# audioRev5.net
KiCad netlist of a schematic drawn in EAGLE
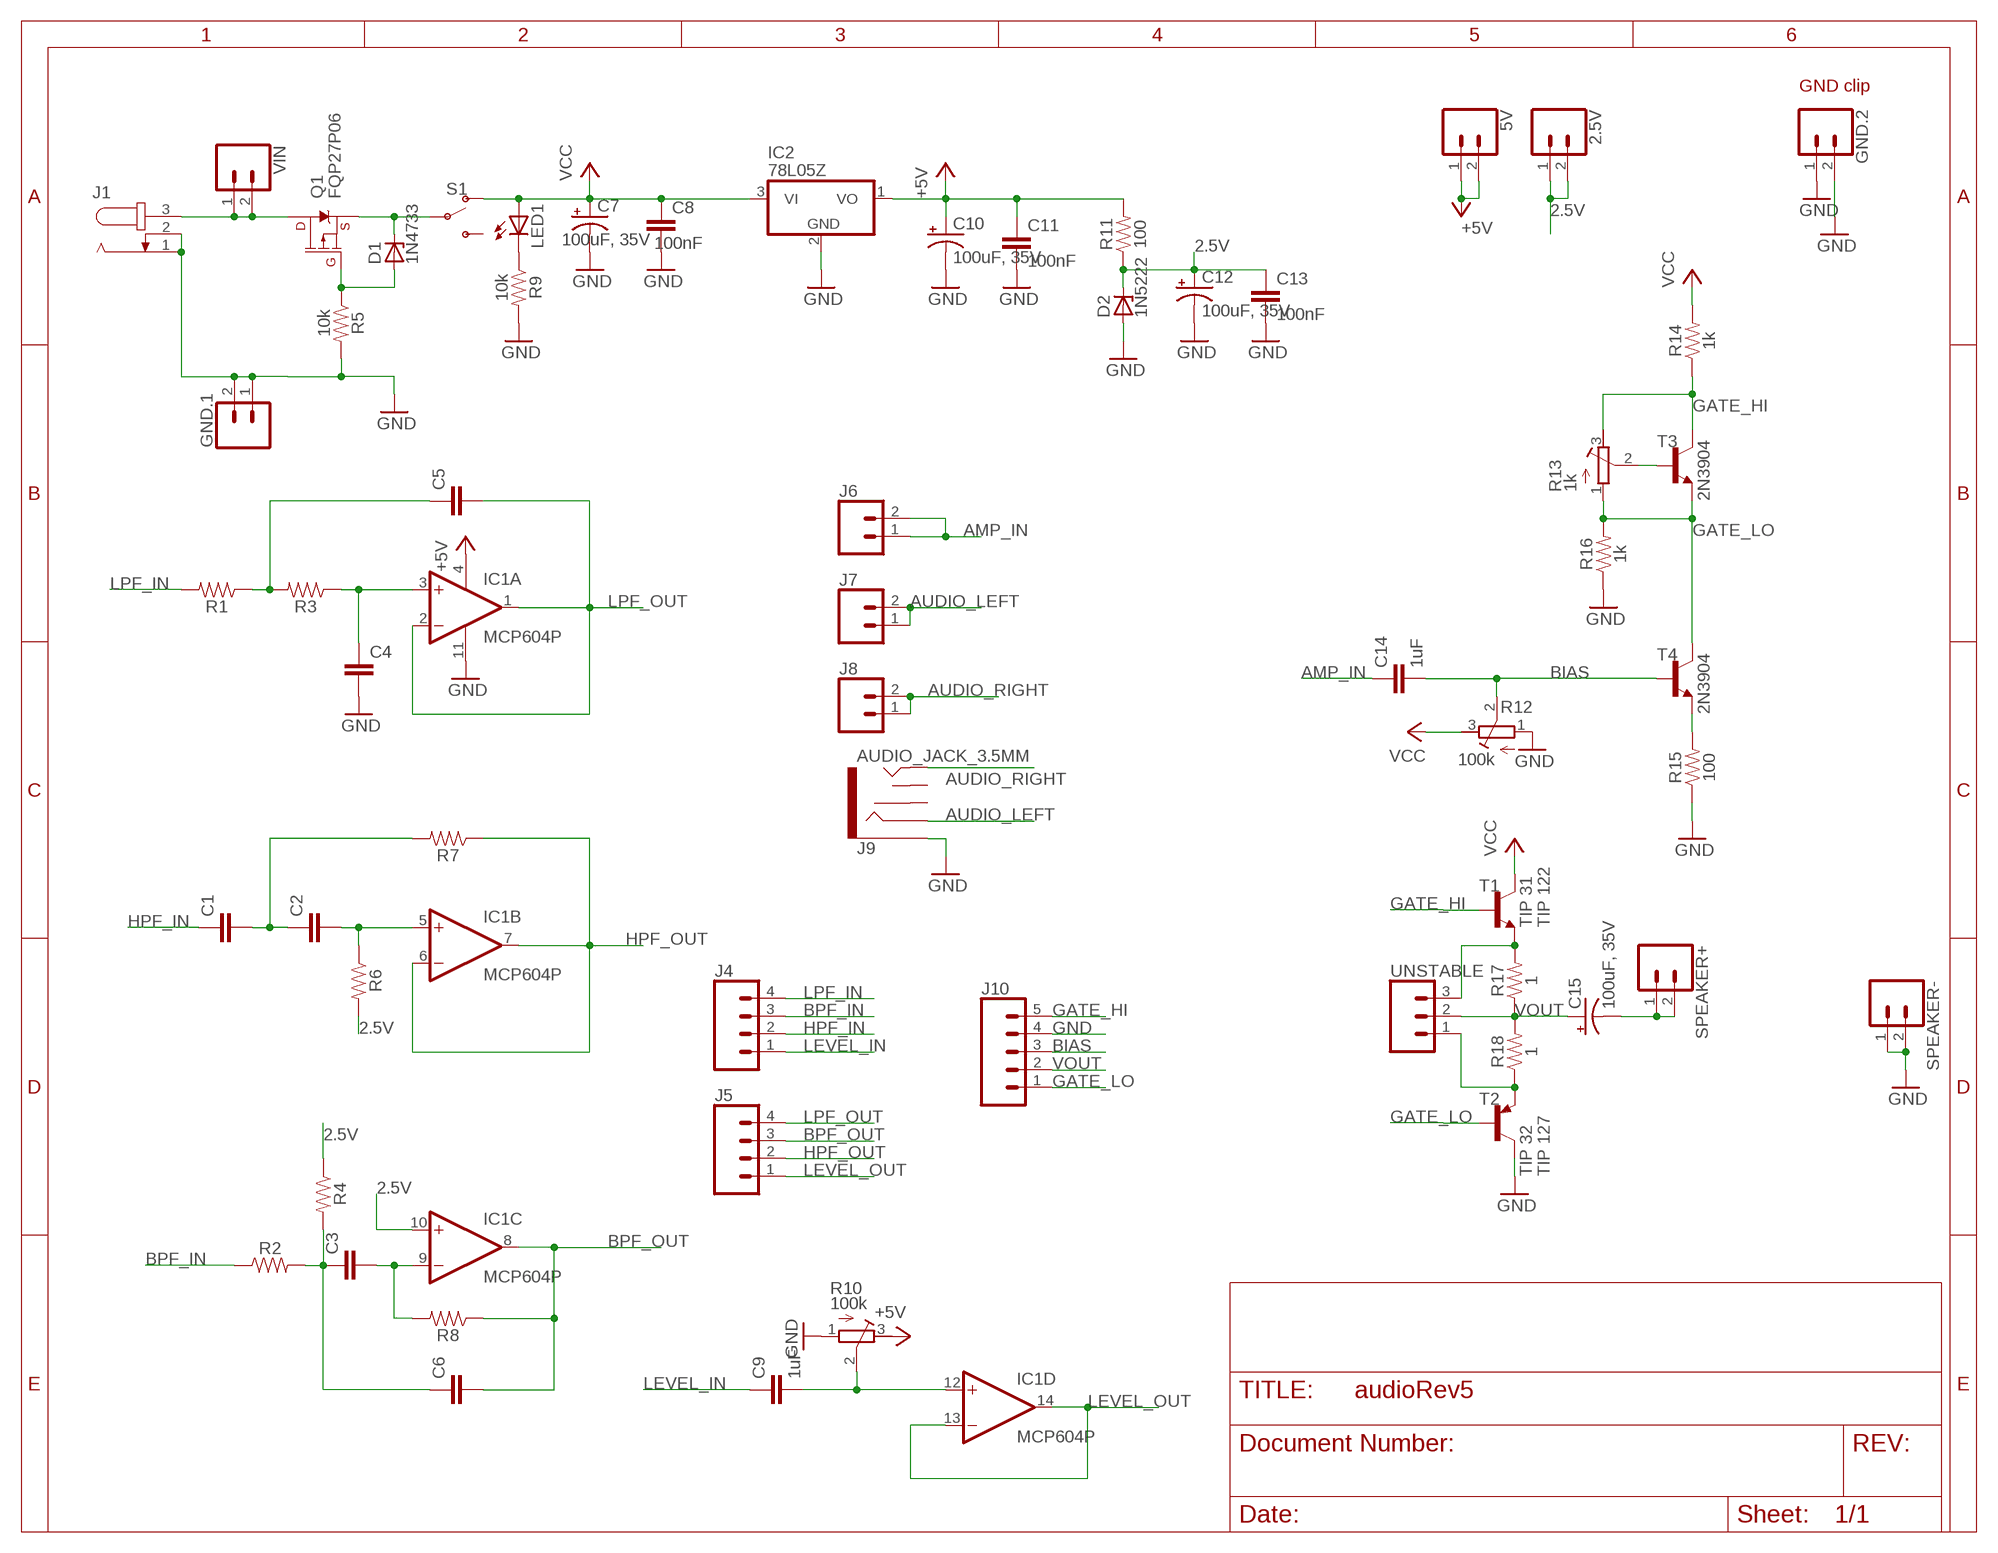
[diagram p0: schematic, sheet 1]

(export (version "E")
  (design (tool "Eeschema 10.0.6"))
  (components
    (comp (ref "2.5V")
      (value "CONN_02")
      (footprint "eagle-import:1X02")
      (libsource (lib "eagle-import") (part "CONN_02"))
    )
    (comp (ref "5V")
      (value "CONN_02")
      (footprint "eagle-import:1X02")
      (libsource (lib "eagle-import") (part "CONN_02"))
    )
    (comp (ref "C1")
      (value "C-EU025-025X050")
      (footprint "eagle-import:C025-025X050")
      (libsource (lib "eagle-import") (part "C-EU025-025X050"))
    )
    (comp (ref "C2")
      (value "C-EU025-025X050")
      (footprint "eagle-import:C025-025X050")
      (libsource (lib "eagle-import") (part "C-EU025-025X050"))
    )
    (comp (ref "C3")
      (value "C-EU025-025X050")
      (footprint "eagle-import:C025-025X050")
      (libsource (lib "eagle-import") (part "C-EU025-025X050"))
    )
    (comp (ref "C4")
      (value "C-EU025-025X050")
      (footprint "eagle-import:C025-025X050")
      (libsource (lib "eagle-import") (part "C-EU025-025X050"))
    )
    (comp (ref "C5")
      (value "C-EU025-025X050")
      (footprint "eagle-import:C025-025X050")
      (libsource (lib "eagle-import") (part "C-EU025-025X050"))
    )
    (comp (ref "C6")
      (value "C-EU025-025X050")
      (footprint "eagle-import:C025-025X050")
      (libsource (lib "eagle-import") (part "C-EU025-025X050"))
    )
    (comp (ref "C7")
      (value "100uF, 35V")
      (footprint "eagle-import:E2,5-6")
      (libsource (lib "eagle-import") (part "CPOL-USE2.5-6"))
    )
    (comp (ref "C8")
      (value "100nF")
      (footprint "eagle-import:C025-025X050")
      (libsource (lib "eagle-import") (part "C-EU025-025X050"))
    )
    (comp (ref "C9")
      (value "1uF")
      (footprint "eagle-import:C025-025X050")
      (libsource (lib "eagle-import") (part "C-EU025-025X050"))
    )
    (comp (ref "C10")
      (value "100uF, 35V")
      (footprint "eagle-import:E2,5-6")
      (libsource (lib "eagle-import") (part "CPOL-USE2.5-6"))
    )
    (comp (ref "C11")
      (value "100nF")
      (footprint "eagle-import:C025-025X050")
      (libsource (lib "eagle-import") (part "C-EU025-025X050"))
    )
    (comp (ref "C12")
      (value "100uF, 35V")
      (footprint "eagle-import:E2,5-6")
      (libsource (lib "eagle-import") (part "CPOL-USE2.5-6"))
    )
    (comp (ref "C13")
      (value "100nF")
      (footprint "eagle-import:C025-025X050")
      (libsource (lib "eagle-import") (part "C-EU025-025X050"))
    )
    (comp (ref "C14")
      (value "1uF")
      (footprint "eagle-import:C025-025X050")
      (libsource (lib "eagle-import") (part "C-EU025-025X050"))
    )
    (comp (ref "C15")
      (value "100uF, 35V")
      (footprint "eagle-import:E2,5-6")
      (libsource (lib "eagle-import") (part "CPOL-USE2.5-6"))
    )
    (comp (ref "D1")
      (value "1N4733")
      (footprint "eagle-import:DO41Z10")
      (libsource (lib "eagle-import") (part "ZENER-DIODEDO41Z10"))
    )
    (comp (ref "D2")
      (value "1N5222")
      (footprint "eagle-import:DO34Z7")
      (libsource (lib "eagle-import") (part "ZENER-DIODEDO34-7"))
    )
    (comp (ref "GND.1")
      (value "CONN_02")
      (footprint "eagle-import:1X02")
      (libsource (lib "eagle-import") (part "CONN_02"))
    )
    (comp (ref "GND.2")
      (value "CONN_02")
      (footprint "eagle-import:1X02")
      (libsource (lib "eagle-import") (part "CONN_02"))
    )
    (comp (ref "IC1")
      (value "MCP604P")
      (footprint "eagle-import:DIL14")
      (libsource (lib "eagle-import") (part "MCP604P"))
    )
    (comp (ref "IC2")
      (value "78L05Z")
      (footprint "eagle-import:TO92")
      (libsource (lib "eagle-import") (part "78ZL05"))
    )
    (comp (ref "J1")
      (value "JACK-PLUG0")
      (footprint "eagle-import:SPC4077")
      (libsource (lib "eagle-import") (part "JACK-PLUG0"))
    )
    (comp (ref "J4")
      (value "CONN_04LOCK_LONGPADS")
      (footprint "eagle-import:1X04_LOCK_LONGPADS")
      (libsource (lib "eagle-import") (part "CONN_04LOCK_LONGPADS"))
    )
    (comp (ref "J5")
      (value "CONN_04LOCK_LONGPADS")
      (footprint "eagle-import:1X04_LOCK_LONGPADS")
      (libsource (lib "eagle-import") (part "CONN_04LOCK_LONGPADS"))
    )
    (comp (ref "J6")
      (value "CONN_02")
      (footprint "eagle-import:1X02")
      (libsource (lib "eagle-import") (part "CONN_02"))
    )
    (comp (ref "J7")
      (value "CONN_02")
      (footprint "eagle-import:1X02")
      (libsource (lib "eagle-import") (part "CONN_02"))
    )
    (comp (ref "J8")
      (value "CONN_02")
      (footprint "eagle-import:1X02")
      (libsource (lib "eagle-import") (part "CONN_02"))
    )
    (comp (ref "J9")
      (value "AUDIO_JACK_3.5MM")
      (footprint "eagle-import:AUDIO-JACK")
      (libsource (lib "eagle-import") (part "AUDIO_JACK_3.5MM_PTH"))
    )
    (comp (ref "J10")
      (value "CONN_05PTH_LONGPADS")
      (footprint "eagle-import:1X05_LONGPADS")
      (libsource (lib "eagle-import") (part "CONN_05PTH_LONGPADS"))
    )
    (comp (ref "LED1")
      (value "LED5MM")
      (footprint "eagle-import:LED5MM")
      (libsource (lib "eagle-import") (part "LED5MM"))
    )
    (comp (ref "Q1")
      (value "FQP27P06")
      (footprint "eagle-import:TO220V")
      (libsource (lib "eagle-import") (part "MOSFET_PCH-NDP6020P"))
    )
    (comp (ref "R1")
      (value "RESISTORAXIAL-0.3")
      (footprint "eagle-import:AXIAL-0.3")
      (libsource (lib "eagle-import") (part "RESISTORAXIAL-0.3"))
    )
    (comp (ref "R2")
      (value "RESISTORAXIAL-0.3")
      (footprint "eagle-import:AXIAL-0.3")
      (libsource (lib "eagle-import") (part "RESISTORAXIAL-0.3"))
    )
    (comp (ref "R3")
      (value "RESISTORAXIAL-0.3")
      (footprint "eagle-import:AXIAL-0.3")
      (libsource (lib "eagle-import") (part "RESISTORAXIAL-0.3"))
    )
    (comp (ref "R4")
      (value "RESISTORAXIAL-0.3")
      (footprint "eagle-import:AXIAL-0.3")
      (libsource (lib "eagle-import") (part "RESISTORAXIAL-0.3"))
    )
    (comp (ref "R5")
      (value "10k")
      (footprint "eagle-import:AXIAL-0.3")
      (libsource (lib "eagle-import") (part "RESISTORAXIAL-0.3"))
    )
    (comp (ref "R6")
      (value "RESISTORAXIAL-0.3")
      (footprint "eagle-import:AXIAL-0.3")
      (libsource (lib "eagle-import") (part "RESISTORAXIAL-0.3"))
    )
    (comp (ref "R7")
      (value "RESISTORAXIAL-0.3")
      (footprint "eagle-import:AXIAL-0.3")
      (libsource (lib "eagle-import") (part "RESISTORAXIAL-0.3"))
    )
    (comp (ref "R8")
      (value "RESISTORAXIAL-0.3")
      (footprint "eagle-import:AXIAL-0.3")
      (libsource (lib "eagle-import") (part "RESISTORAXIAL-0.3"))
    )
    (comp (ref "R9")
      (value "10k")
      (footprint "eagle-import:AXIAL-0.3")
      (libsource (lib "eagle-import") (part "RESISTORAXIAL-0.3"))
    )
    (comp (ref "R10")
      (value "100k")
      (footprint "eagle-import:RTRIM3296W")
      (libsource (lib "eagle-import") (part "R-TRIMM3296W"))
    )
    (comp (ref "R11")
      (value "100")
      (footprint "eagle-import:AXIAL-0.3")
      (libsource (lib "eagle-import") (part "RESISTORAXIAL-0.3"))
    )
    (comp (ref "R12")
      (value "100k")
      (footprint "eagle-import:RTRIM3296W")
      (libsource (lib "eagle-import") (part "R-TRIMM3296W"))
    )
    (comp (ref "R13")
      (value "1k")
      (footprint "eagle-import:RTRIM3296W")
      (libsource (lib "eagle-import") (part "R-TRIMM3296W"))
    )
    (comp (ref "R14")
      (value "1k")
      (footprint "eagle-import:AXIAL-0.3")
      (libsource (lib "eagle-import") (part "RESISTORAXIAL-0.3"))
    )
    (comp (ref "R15")
      (value "100")
      (footprint "eagle-import:AXIAL-0.3")
      (libsource (lib "eagle-import") (part "RESISTORAXIAL-0.3"))
    )
    (comp (ref "R16")
      (value "1k")
      (footprint "eagle-import:AXIAL-0.3")
      (libsource (lib "eagle-import") (part "RESISTORAXIAL-0.3"))
    )
    (comp (ref "R17")
      (value "1")
      (footprint "eagle-import:AXIAL-0.3")
      (libsource (lib "eagle-import") (part "RESISTORAXIAL-0.3"))
    )
    (comp (ref "R18")
      (value "1")
      (footprint "eagle-import:AXIAL-0.3")
      (libsource (lib "eagle-import") (part "RESISTORAXIAL-0.3"))
    )
    (comp (ref "S1")
      (value "SWITCH-SPDT-PTH-11.6X4.0MM")
      (footprint "eagle-import:SWITCH_SPDT_PTH_11.6X4.0MM")
      (libsource (lib "eagle-import") (part "SWITCH-SPDT-PTH-11.6X4.0MM"))
    )
    (comp (ref "SPEAKER+")
      (value "CONN_02")
      (footprint "eagle-import:1X02")
      (libsource (lib "eagle-import") (part "CONN_02"))
    )
    (comp (ref "SPEAKER-")
      (value "CONN_02")
      (footprint "eagle-import:1X02")
      (libsource (lib "eagle-import") (part "CONN_02"))
    )
    (comp (ref "T1")
      (value "TIP 31")
      (footprint "eagle-import:TO220V")
      (libsource (lib "eagle-import") (part "-NPN-TO220V"))
    )
    (comp (ref "T2")
      (value "TIP 32")
      (footprint "eagle-import:TO220V")
      (libsource (lib "eagle-import") (part "-PNP-TO220V"))
    )
    (comp (ref "T3")
      (value "2N3904")
      (footprint "eagle-import:TO92-EBC")
      (libsource (lib "eagle-import") (part "-NPN-TO92-EBC"))
    )
    (comp (ref "T4")
      (value "2N3904")
      (footprint "eagle-import:TO92-EBC")
      (libsource (lib "eagle-import") (part "-NPN-TO92-EBC"))
    )
    (comp (ref "UNSTABLE")
      (value "CONN_03LOCK_LONGPADS")
      (footprint "eagle-import:1X03_LOCK_LONGPADS")
      (libsource (lib "eagle-import") (part "CONN_03LOCK_LONGPADS"))
    )
    (comp (ref "VIN")
      (value "CONN_02")
      (footprint "eagle-import:1X02")
      (libsource (lib "eagle-import") (part "CONN_02"))
    )
  )
  (nets
    (net (code "1") (name "+5V") (class "Default")
      (node (ref "5V") (pin "1") (pinfunction "1_1") (pintype "passive"))
      (node (ref "5V") (pin "2") (pinfunction "2_2") (pintype "passive"))
      (node (ref "C10") (pin "+") (pinfunction "+_+") (pintype "passive"))
      (node (ref "C11") (pin "1") (pinfunction "1_1") (pintype "passive"))
      (node (ref "IC1") (pin "4") (pinfunction "V+_4") (pintype "power_in"))
      (node (ref "IC2") (pin "1") (pinfunction "VO_1") (pintype "passive"))
      (node (ref "R10") (pin "3") (pinfunction "E_3") (pintype "passive"))
      (node (ref "R11") (pin "P$2") (pinfunction "2_P$2") (pintype "passive"))
    )
    (net (code "2") (name "/2.5V") (class "Default")
      (node (ref "2.5V") (pin "1") (pinfunction "1_1") (pintype "passive"))
      (node (ref "2.5V") (pin "2") (pinfunction "2_2") (pintype "passive"))
      (node (ref "C12") (pin "+") (pinfunction "+_+") (pintype "passive"))
      (node (ref "C13") (pin "1") (pinfunction "1_1") (pintype "passive"))
      (node (ref "D2") (pin "C") (pinfunction "C_C") (pintype "passive"))
      (node (ref "IC1") (pin "10") (pinfunction "+IN_10") (pintype "input"))
      (node (ref "R11") (pin "P$1") (pinfunction "1_P$1") (pintype "passive"))
      (node (ref "R4") (pin "P$1") (pinfunction "1_P$1") (pintype "passive"))
      (node (ref "R6") (pin "P$2") (pinfunction "2_P$2") (pintype "passive"))
    )
    (net (code "3") (name "/AMP_IN") (class "Default")
      (node (ref "C14") (pin "1") (pinfunction "1_1") (pintype "passive"))
      (node (ref "J6") (pin "1") (pinfunction "1_1") (pintype "passive"))
      (node (ref "J6") (pin "2") (pinfunction "2_2") (pintype "passive"))
    )
    (net (code "4") (name "/AUDIO_LEFT") (class "Default")
      (node (ref "J7") (pin "1") (pinfunction "1_1") (pintype "passive"))
      (node (ref "J7") (pin "2") (pinfunction "2_2") (pintype "passive"))
      (node (ref "J9") (pin "RING") (pinfunction "RING_RING") (pintype "bidirectional"))
    )
    (net (code "5") (name "/AUDIO_RIGHT") (class "Default")
      (node (ref "J8") (pin "1") (pinfunction "1_1") (pintype "passive"))
      (node (ref "J8") (pin "2") (pinfunction "2_2") (pintype "passive"))
      (node (ref "J9") (pin "TIP") (pinfunction "TIP_TIP") (pintype "bidirectional"))
    )
    (net (code "6") (name "/BIAS") (class "Default")
      (node (ref "C14") (pin "2") (pinfunction "2_2") (pintype "passive"))
      (node (ref "J10") (pin "3") (pinfunction "3_3") (pintype "passive"))
      (node (ref "R12") (pin "2") (pinfunction "S_2") (pintype "passive"))
      (node (ref "T4") (pin "B") (pinfunction "B_B") (pintype "passive"))
    )
    (net (code "7") (name "/BPF_IN") (class "Default")
      (node (ref "J4") (pin "3") (pinfunction "3_3") (pintype "passive"))
      (node (ref "R2") (pin "P$1") (pinfunction "1_P$1") (pintype "passive"))
    )
    (net (code "8") (name "/BPF_OUT") (class "Default")
      (node (ref "C6") (pin "2") (pinfunction "2_2") (pintype "passive"))
      (node (ref "IC1") (pin "8") (pinfunction "OUT_8") (pintype "output"))
      (node (ref "J5") (pin "3") (pinfunction "3_3") (pintype "passive"))
      (node (ref "R8") (pin "P$1") (pinfunction "1_P$1") (pintype "passive"))
    )
    (net (code "9") (name "/GATE_HI") (class "Default")
      (node (ref "J10") (pin "5") (pinfunction "5_5") (pintype "passive"))
      (node (ref "R13") (pin "3") (pinfunction "E_3") (pintype "passive"))
      (node (ref "R14") (pin "P$1") (pinfunction "1_P$1") (pintype "passive"))
      (node (ref "T1") (pin "1") (pinfunction "B_1") (pintype "passive"))
      (node (ref "T3") (pin "C") (pinfunction "C_C") (pintype "passive"))
    )
    (net (code "10") (name "/GATE_LO") (class "Default")
      (node (ref "J10") (pin "1") (pinfunction "1_1") (pintype "passive"))
      (node (ref "R13") (pin "1") (pinfunction "A_1") (pintype "passive"))
      (node (ref "R16") (pin "P$2") (pinfunction "2_P$2") (pintype "passive"))
      (node (ref "T2") (pin "1") (pinfunction "B_1") (pintype "passive"))
      (node (ref "T3") (pin "E") (pinfunction "E_E") (pintype "passive"))
      (node (ref "T4") (pin "C") (pinfunction "C_C") (pintype "passive"))
    )
    (net (code "11") (name "/HPF_IN") (class "Default")
      (node (ref "C1") (pin "1") (pinfunction "1_1") (pintype "passive"))
      (node (ref "J4") (pin "2") (pinfunction "2_2") (pintype "passive"))
    )
    (net (code "12") (name "/HPF_OUT") (class "Default")
      (node (ref "IC1") (pin "6") (pinfunction "-IN_6") (pintype "input"))
      (node (ref "IC1") (pin "7") (pinfunction "OUT_7") (pintype "output"))
      (node (ref "J5") (pin "2") (pinfunction "2_2") (pintype "passive"))
      (node (ref "R7") (pin "P$1") (pinfunction "1_P$1") (pintype "passive"))
    )
    (net (code "13") (name "/LEVEL_IN") (class "Default")
      (node (ref "C9") (pin "1") (pinfunction "1_1") (pintype "passive"))
      (node (ref "J4") (pin "1") (pinfunction "1_1") (pintype "passive"))
    )
    (net (code "14") (name "/LEVEL_OUT") (class "Default")
      (node (ref "IC1") (pin "13") (pinfunction "-IN_13") (pintype "input"))
      (node (ref "IC1") (pin "14") (pinfunction "OUT_14") (pintype "output"))
      (node (ref "J5") (pin "1") (pinfunction "1_1") (pintype "passive"))
    )
    (net (code "15") (name "/LPF_IN") (class "Default")
      (node (ref "J4") (pin "4") (pinfunction "4_4") (pintype "passive"))
      (node (ref "R1") (pin "P$2") (pinfunction "2_P$2") (pintype "passive"))
    )
    (net (code "16") (name "/LPF_OUT") (class "Default")
      (node (ref "C5") (pin "2") (pinfunction "2_2") (pintype "passive"))
      (node (ref "IC1") (pin "1") (pinfunction "OUT_1") (pintype "output"))
      (node (ref "IC1") (pin "2") (pinfunction "-IN_2") (pintype "input"))
      (node (ref "J5") (pin "4") (pinfunction "4_4") (pintype "passive"))
    )
    (net (code "17") (name "/VOUT") (class "Default")
      (node (ref "C15") (pin "+") (pinfunction "+_+") (pintype "passive"))
      (node (ref "J10") (pin "2") (pinfunction "2_2") (pintype "passive"))
      (node (ref "R17") (pin "P$1") (pinfunction "1_P$1") (pintype "passive"))
      (node (ref "R18") (pin "P$2") (pinfunction "2_P$2") (pintype "passive"))
      (node (ref "UNSTABLE") (pin "2") (pinfunction "2_2") (pintype "passive"))
    )
    (net (code "18") (name "GND") (class "Default")
      (node (ref "C10") (pin "-") (pinfunction "-_-") (pintype "passive"))
      (node (ref "C11") (pin "2") (pinfunction "2_2") (pintype "passive"))
      (node (ref "C12") (pin "-") (pinfunction "-_-") (pintype "passive"))
      (node (ref "C13") (pin "2") (pinfunction "2_2") (pintype "passive"))
      (node (ref "C4") (pin "2") (pinfunction "2_2") (pintype "passive"))
      (node (ref "C7") (pin "-") (pinfunction "-_-") (pintype "passive"))
      (node (ref "C8") (pin "2") (pinfunction "2_2") (pintype "passive"))
      (node (ref "D2") (pin "A") (pinfunction "A_A") (pintype "passive"))
      (node (ref "GND.1") (pin "1") (pinfunction "1_1") (pintype "passive"))
      (node (ref "GND.1") (pin "2") (pinfunction "2_2") (pintype "passive"))
      (node (ref "GND.2") (pin "1") (pinfunction "1_1") (pintype "passive"))
      (node (ref "GND.2") (pin "2") (pinfunction "2_2") (pintype "passive"))
      (node (ref "IC1") (pin "11") (pinfunction "V-_11") (pintype "power_in"))
      (node (ref "IC2") (pin "2") (pinfunction "GND_2") (pintype "passive"))
      (node (ref "J1") (pin "1") (pinfunction "1_1") (pintype "passive"))
      (node (ref "J1") (pin "2") (pinfunction "2_2") (pintype "passive"))
      (node (ref "J10") (pin "4") (pinfunction "4_4") (pintype "passive"))
      (node (ref "J9") (pin "SLEEVE") (pinfunction "SLEEVE_SLEEVE") (pintype "bidirectional"))
      (node (ref "R10") (pin "1") (pinfunction "A_1") (pintype "passive"))
      (node (ref "R12") (pin "1") (pinfunction "A_1") (pintype "passive"))
      (node (ref "R15") (pin "P$1") (pinfunction "1_P$1") (pintype "passive"))
      (node (ref "R16") (pin "P$1") (pinfunction "1_P$1") (pintype "passive"))
      (node (ref "R5") (pin "P$2") (pinfunction "2_P$2") (pintype "passive"))
      (node (ref "R9") (pin "P$2") (pinfunction "2_P$2") (pintype "passive"))
      (node (ref "SPEAKER-") (pin "1") (pinfunction "1_1") (pintype "passive"))
      (node (ref "SPEAKER-") (pin "2") (pinfunction "2_2") (pintype "passive"))
      (node (ref "T2") (pin "2") (pinfunction "C_2") (pintype "passive"))
    )
    (net (code "19") (name "Net-(C15-Pad-)") (class "Default")
      (node (ref "C15") (pin "-") (pinfunction "-_-") (pintype "passive"))
      (node (ref "SPEAKER+") (pin "1") (pinfunction "1_1") (pintype "passive"))
      (node (ref "SPEAKER+") (pin "2") (pinfunction "2_2") (pintype "passive"))
    )
    (net (code "20") (name "Net-(IC1A-+IN)") (class "Default")
      (node (ref "C4") (pin "1") (pinfunction "1_1") (pintype "passive"))
      (node (ref "IC1") (pin "3") (pinfunction "+IN_3") (pintype "input"))
      (node (ref "R3") (pin "P$1") (pinfunction "1_P$1") (pintype "passive"))
    )
    (net (code "21") (name "Net-(IC1B-+IN)") (class "Default")
      (node (ref "C2") (pin "2") (pinfunction "2_2") (pintype "passive"))
      (node (ref "IC1") (pin "5") (pinfunction "+IN_5") (pintype "input"))
      (node (ref "R6") (pin "P$1") (pinfunction "1_P$1") (pintype "passive"))
    )
    (net (code "22") (name "Net-(IC1C--IN)") (class "Default")
      (node (ref "C3") (pin "2") (pinfunction "2_2") (pintype "passive"))
      (node (ref "IC1") (pin "9") (pinfunction "-IN_9") (pintype "input"))
      (node (ref "R8") (pin "P$2") (pinfunction "2_P$2") (pintype "passive"))
    )
    (net (code "23") (name "Net-(IC1D-+IN)") (class "Default")
      (node (ref "C9") (pin "2") (pinfunction "2_2") (pintype "passive"))
      (node (ref "IC1") (pin "12") (pinfunction "+IN_12") (pintype "input"))
      (node (ref "R10") (pin "2") (pinfunction "S_2") (pintype "passive"))
    )
    (net (code "24") (name "Net-(LED1-C)") (class "Default")
      (node (ref "LED1") (pin "K") (pinfunction "C_K") (pintype "passive"))
      (node (ref "R9") (pin "P$1") (pinfunction "1_P$1") (pintype "passive"))
    )
    (net (code "25") (name "Net-(Q1-D)") (class "Default")
      (node (ref "J1") (pin "3") (pinfunction "3_3") (pintype "passive"))
      (node (ref "Q1") (pin "2") (pinfunction "D_2") (pintype "bidirectional"))
      (node (ref "VIN") (pin "1") (pinfunction "1_1") (pintype "passive"))
      (node (ref "VIN") (pin "2") (pinfunction "2_2") (pintype "passive"))
    )
    (net (code "26") (name "Net-(Q1-G)") (class "Default")
      (node (ref "D1") (pin "A") (pinfunction "A_A") (pintype "passive"))
      (node (ref "Q1") (pin "1") (pinfunction "G_1") (pintype "bidirectional"))
      (node (ref "R5") (pin "P$1") (pinfunction "1_P$1") (pintype "passive"))
    )
    (net (code "27") (name "Net-(Q1-S)") (class "Default")
      (node (ref "D1") (pin "C") (pinfunction "C_C") (pintype "passive"))
      (node (ref "Q1") (pin "3") (pinfunction "S_3") (pintype "bidirectional"))
      (node (ref "S1") (pin "2") (pinfunction "P_2") (pintype "passive"))
    )
    (net (code "28") (name "Net-(R1-1)") (class "Default")
      (node (ref "C5") (pin "1") (pinfunction "1_1") (pintype "passive"))
      (node (ref "R1") (pin "P$1") (pinfunction "1_P$1") (pintype "passive"))
      (node (ref "R3") (pin "P$2") (pinfunction "2_P$2") (pintype "passive"))
    )
    (net (code "29") (name "Net-(R2-2)") (class "Default")
      (node (ref "C3") (pin "1") (pinfunction "1_1") (pintype "passive"))
      (node (ref "C6") (pin "1") (pinfunction "1_1") (pintype "passive"))
      (node (ref "R2") (pin "P$2") (pinfunction "2_P$2") (pintype "passive"))
      (node (ref "R4") (pin "P$2") (pinfunction "2_P$2") (pintype "passive"))
    )
    (net (code "30") (name "Net-(R7-2)") (class "Default")
      (node (ref "C1") (pin "2") (pinfunction "2_2") (pintype "passive"))
      (node (ref "C2") (pin "1") (pinfunction "1_1") (pintype "passive"))
      (node (ref "R7") (pin "P$2") (pinfunction "2_P$2") (pintype "passive"))
    )
    (net (code "31") (name "Net-(R13-S)") (class "Default")
      (node (ref "R13") (pin "2") (pinfunction "S_2") (pintype "passive"))
      (node (ref "T3") (pin "B") (pinfunction "B_B") (pintype "passive"))
    )
    (net (code "32") (name "Net-(R15-2)") (class "Default")
      (node (ref "R15") (pin "P$2") (pinfunction "2_P$2") (pintype "passive"))
      (node (ref "T4") (pin "E") (pinfunction "E_E") (pintype "passive"))
    )
    (net (code "33") (name "Net-(R17-2)") (class "Default")
      (node (ref "R17") (pin "P$2") (pinfunction "2_P$2") (pintype "passive"))
      (node (ref "T1") (pin "3") (pinfunction "E_3") (pintype "passive"))
      (node (ref "UNSTABLE") (pin "3") (pinfunction "3_3") (pintype "passive"))
    )
    (net (code "34") (name "Net-(R18-1)") (class "Default")
      (node (ref "R18") (pin "P$1") (pinfunction "1_P$1") (pintype "passive"))
      (node (ref "T2") (pin "3") (pinfunction "E_3") (pintype "passive"))
      (node (ref "UNSTABLE") (pin "1") (pinfunction "1_1") (pintype "passive"))
    )
    (net (code "35") (name "VCC") (class "Default")
      (node (ref "C7") (pin "+") (pinfunction "+_+") (pintype "passive"))
      (node (ref "C8") (pin "1") (pinfunction "1_1") (pintype "passive"))
      (node (ref "IC2") (pin "3") (pinfunction "VI_3") (pintype "input"))
      (node (ref "LED1") (pin "A") (pinfunction "A_A") (pintype "passive"))
      (node (ref "R12") (pin "3") (pinfunction "E_3") (pintype "passive"))
      (node (ref "R14") (pin "P$2") (pinfunction "2_P$2") (pintype "passive"))
      (node (ref "S1") (pin "1") (pinfunction "O_1") (pintype "passive"))
      (node (ref "T1") (pin "2") (pinfunction "C_2") (pintype "passive"))
    )
    (net (code "36") (name "unconnected-(J9-PadRSH)") (class "Default")
      (node (ref "J9") (pin "RSH") (pinfunction "RSH_RSH") (pintype "bidirectional"))
    )
    (net (code "37") (name "unconnected-(J9-PadTSH)") (class "Default")
      (node (ref "J9") (pin "TSH") (pinfunction "TSH_TSH") (pintype "bidirectional"))
    )
    (net (code "38") (name "unconnected-(S1-S-Pad3)") (class "Default")
      (node (ref "S1") (pin "3") (pinfunction "S_3") (pintype "passive"))
    )
  )
)
